# MTSensorV2_1.net
KiCad netlist of a schematic drawn in EAGLE
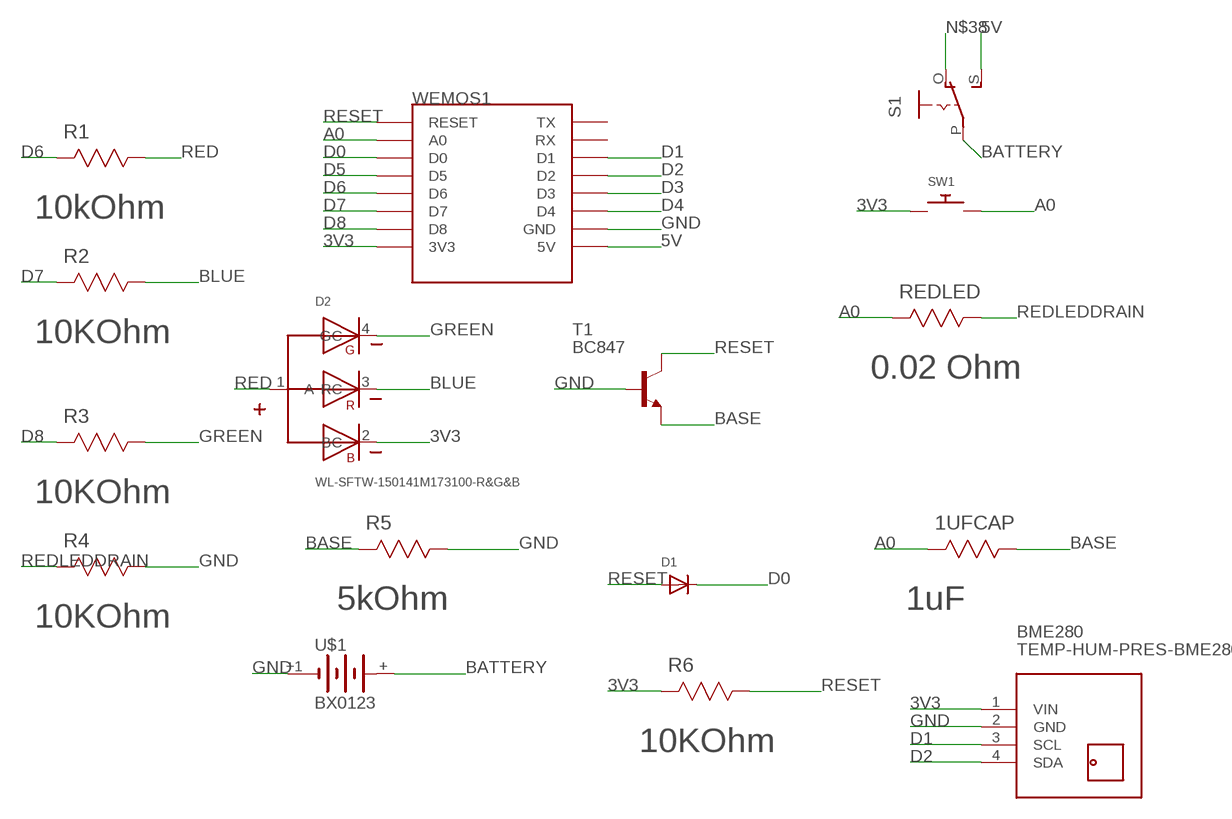
[diagram p0: schematic, sheet 1]

(export (version "E")
  (design (tool "Eeschema 10.0.6"))
  (components
    (comp (ref "1UFCAP")
      (value "1uF")
      (footprint "eagle-import:RESC1608X60N")
      (fields (field (name "MPN") "ERA-3AEB101V") (field (name "TOLERANCE") "±0.1%"))
      (libsource (lib "eagle-import") (part "ERA-3AEB101V"))
    )
    (comp (ref "BME280")
      (value "TEMP-HUM-PRES-BME280")
      (footprint "eagle-import:TEMP-HUM-PRES-BME280")
      (libsource (lib "eagle-import") (part "TEMP-HUM-PRES-BME280"))
    )
    (comp (ref "D1")
      (value "DIODESOD-123")
      (footprint "eagle-import:SOD-123")
      (libsource (lib "eagle-import") (part "DIODESOD-123"))
    )
    (comp (ref "D2")
      (value "WL-SFTW-150141M173100-R&G&B")
      (footprint "eagle-import:3528-COMMON-ANODE")
      (libsource (lib "eagle-import") (part "WL-SFTW-150141M173100-R&G&B"))
    )
    (comp (ref "R1")
      (value "10kOhm")
      (footprint "eagle-import:RESC3216X71N")
      (fields (field (name "MPN") "ERJ-8BWFR010V") (field (name "TOLERANCE") "± 1 %"))
      (libsource (lib "eagle-import") (part "ERJ-8BWFR010V"))
    )
    (comp (ref "R2")
      (value "10KOhm")
      (footprint "eagle-import:RESC3216X71N")
      (fields (field (name "MPN") "ERJ-8BWFR010V") (field (name "TOLERANCE") "± 1 %"))
      (libsource (lib "eagle-import") (part "ERJ-8BWFR010V"))
    )
    (comp (ref "R3")
      (value "10KOhm")
      (footprint "eagle-import:RESC3216X71N")
      (fields (field (name "MPN") "ERJ-8BWFR010V") (field (name "TOLERANCE") "± 1 %"))
      (libsource (lib "eagle-import") (part "ERJ-8BWFR010V"))
    )
    (comp (ref "R4")
      (value "10KOhm")
      (footprint "eagle-import:RESC3216X71N")
      (fields (field (name "MPN") "ERJ-8BWFR010V") (field (name "TOLERANCE") "± 1 %"))
      (libsource (lib "eagle-import") (part "ERJ-8BWFR010V"))
    )
    (comp (ref "R5")
      (value "5kOhm")
      (footprint "eagle-import:RESC3216X71N")
      (fields (field (name "MPN") "ERJ-8BWFR011V") (field (name "TOLERANCE") "± 1 %"))
      (libsource (lib "eagle-import") (part "ERJ-8BWFR011V"))
    )
    (comp (ref "R6")
      (value "10KOhm")
      (footprint "eagle-import:RESC3216X71N")
      (fields (field (name "MPN") "ERJ-8BWFR010V") (field (name "TOLERANCE") "± 1 %"))
      (libsource (lib "eagle-import") (part "ERJ-8BWFR010V"))
    )
    (comp (ref "REDLED")
      (value "0.02 Ohm")
      (footprint "eagle-import:RESC3216X71N")
      (fields (field (name "MPN") "ERJ-8BWFR030V") (field (name "TOLERANCE") "± 1 %"))
      (libsource (lib "eagle-import") (part "ERJ-8BWFR030V"))
    )
    (comp (ref "S1")
      (value "EG1218S")
      (footprint "eagle-import:EG1218")
      (libsource (lib "eagle-import") (part "EG1218S"))
    )
    (comp (ref "SW1")
      (value "SWITCH_PUSHBUTTONEVQ-PE")
      (footprint "eagle-import:TACT_PANA-EVQ")
      (libsource (lib "eagle-import") (part "SWITCH_PUSHBUTTONEVQ-PE"))
    )
    (comp (ref "T1")
      (value "BC847")
      (footprint "eagle-import:SOT23")
      (libsource (lib "eagle-import") (part "BC847"))
    )
    (comp (ref "U$1")
      (value "BX0123")
      (footprint "eagle-import:CR123A_HOLDER")
      (fields (field (name "MF") "Bulgin"))
      (libsource (lib "eagle-import") (part "BX0123"))
    )
    (comp (ref "WEMOS1")
      (value "WEMOS-D1-MINI")
      (footprint "eagle-import:WEMOS-D1-MINI")
      (libsource (lib "eagle-import") (part "WEMOS-D1-MINI"))
    )
  )
  (nets
    (net (code "1") (name "/3V3") (class "Default")
      (node (ref "BME280") (pin "1") (pinfunction "VIN_1") (pintype "power_in"))
      (node (ref "D2") (pin "2") (pinfunction "BC_2") (pintype "bidirectional"))
      (node (ref "R6") (pin "2") (pinfunction "R2_2") (pintype "passive"))
      (node (ref "SW1") (pin "P$1") (pinfunction "P$1_P$1") (pintype "passive"))
      (node (ref "WEMOS1") (pin "3V3") (pinfunction "3V3_3V3") (pintype "bidirectional"))
    )
    (net (code "2") (name "/5V") (class "Default")
      (node (ref "S1") (pin "S") (pinfunction "S_S") (pintype "passive"))
      (node (ref "WEMOS1") (pin "5V") (pinfunction "5V_5V") (pintype "bidirectional"))
    )
    (net (code "3") (name "/A0") (class "Default")
      (node (ref "1UFCAP") (pin "2") (pinfunction "R2_2") (pintype "passive"))
      (node (ref "REDLED") (pin "2") (pinfunction "R2_2") (pintype "passive"))
      (node (ref "SW1") (pin "P$2") (pinfunction "P$2_P$2") (pintype "passive"))
      (node (ref "WEMOS1") (pin "A0") (pinfunction "A0_A0") (pintype "bidirectional"))
    )
    (net (code "4") (name "/BASE") (class "Default")
      (node (ref "1UFCAP") (pin "1") (pinfunction "R1_1") (pintype "passive"))
      (node (ref "R5") (pin "2") (pinfunction "R2_2") (pintype "passive"))
      (node (ref "T1") (pin "2") (pinfunction "E_2") (pintype "passive"))
    )
    (net (code "5") (name "/BATTERY") (class "Default")
      (node (ref "S1") (pin "P") (pinfunction "P_P") (pintype "passive"))
      (node (ref "U$1") (pin "+") (pinfunction "+_+") (pintype "passive"))
    )
    (net (code "6") (name "/BLUE") (class "Default")
      (node (ref "D2") (pin "3") (pinfunction "RC_3") (pintype "bidirectional"))
      (node (ref "R2") (pin "1") (pinfunction "R1_1") (pintype "passive"))
    )
    (net (code "7") (name "/D0") (class "Default")
      (node (ref "D1") (pin "C") (pinfunction "C_C") (pintype "passive"))
      (node (ref "WEMOS1") (pin "D0") (pinfunction "D0_D0") (pintype "bidirectional"))
    )
    (net (code "8") (name "/D1") (class "Default")
      (node (ref "BME280") (pin "3") (pinfunction "SCL_3") (pintype "bidirectional"))
      (node (ref "WEMOS1") (pin "D1") (pinfunction "D1_D1") (pintype "bidirectional"))
    )
    (net (code "9") (name "/D2") (class "Default")
      (node (ref "BME280") (pin "4") (pinfunction "SDA_4") (pintype "bidirectional"))
      (node (ref "WEMOS1") (pin "D2") (pinfunction "D2_D2") (pintype "bidirectional"))
    )
    (net (code "10") (name "/D3") (class "Default")
      (node (ref "WEMOS1") (pin "D3") (pinfunction "D3_D3") (pintype "bidirectional"))
    )
    (net (code "11") (name "/D4") (class "Default")
      (node (ref "WEMOS1") (pin "D4") (pinfunction "D4_D4") (pintype "bidirectional"))
    )
    (net (code "12") (name "/D5") (class "Default")
      (node (ref "WEMOS1") (pin "D5") (pinfunction "D5_D5") (pintype "bidirectional"))
    )
    (net (code "13") (name "/D6") (class "Default")
      (node (ref "R1") (pin "2") (pinfunction "R2_2") (pintype "passive"))
      (node (ref "WEMOS1") (pin "D6") (pinfunction "D6_D6") (pintype "bidirectional"))
    )
    (net (code "14") (name "/D7") (class "Default")
      (node (ref "R2") (pin "2") (pinfunction "R2_2") (pintype "passive"))
      (node (ref "WEMOS1") (pin "D7") (pinfunction "D7_D7") (pintype "bidirectional"))
    )
    (net (code "15") (name "/D8") (class "Default")
      (node (ref "R3") (pin "2") (pinfunction "R2_2") (pintype "passive"))
      (node (ref "WEMOS1") (pin "D8") (pinfunction "D8_D8") (pintype "bidirectional"))
    )
    (net (code "16") (name "/GND") (class "Default")
      (node (ref "BME280") (pin "2") (pinfunction "GND_2") (pintype "power_in"))
      (node (ref "R4") (pin "1") (pinfunction "R1_1") (pintype "passive"))
      (node (ref "R5") (pin "1") (pinfunction "R1_1") (pintype "passive"))
      (node (ref "T1") (pin "1") (pinfunction "B_1") (pintype "passive"))
      (node (ref "U$1") (pin "+1") (pinfunction "-_+1") (pintype "passive"))
      (node (ref "WEMOS1") (pin "GND") (pinfunction "GND_GND") (pintype "bidirectional"))
    )
    (net (code "17") (name "/GREEN") (class "Default")
      (node (ref "D2") (pin "4") (pinfunction "GC_4") (pintype "bidirectional"))
      (node (ref "R3") (pin "1") (pinfunction "R1_1") (pintype "passive"))
    )
    (net (code "18") (name "/N$38") (class "Default")
      (node (ref "S1") (pin "O") (pinfunction "O_O") (pintype "passive"))
    )
    (net (code "19") (name "/RED") (class "Default")
      (node (ref "D2") (pin "1") (pinfunction "A_1") (pintype "bidirectional"))
      (node (ref "R1") (pin "1") (pinfunction "R1_1") (pintype "passive"))
    )
    (net (code "20") (name "/REDLEDDRAIN") (class "Default")
      (node (ref "R4") (pin "2") (pinfunction "R2_2") (pintype "passive"))
      (node (ref "REDLED") (pin "1") (pinfunction "R1_1") (pintype "passive"))
    )
    (net (code "21") (name "/RESET") (class "Default")
      (node (ref "D1") (pin "A") (pinfunction "A_A") (pintype "passive"))
      (node (ref "R6") (pin "1") (pinfunction "R1_1") (pintype "passive"))
      (node (ref "T1") (pin "3") (pinfunction "C_3") (pintype "passive"))
      (node (ref "WEMOS1") (pin "RESET") (pinfunction "RESET_RESET") (pintype "bidirectional"))
    )
    (net (code "22") (name "unconnected-(WEMOS1-PadRX)") (class "Default")
      (node (ref "WEMOS1") (pin "RX") (pinfunction "RX_RX") (pintype "bidirectional"))
    )
    (net (code "23") (name "unconnected-(WEMOS1-PadTX)") (class "Default")
      (node (ref "WEMOS1") (pin "TX") (pinfunction "TX_TX") (pintype "bidirectional"))
    )
  )
)
